# FullFuseSchem.net
KiCad netlist of a schematic drawn in Altium Designer
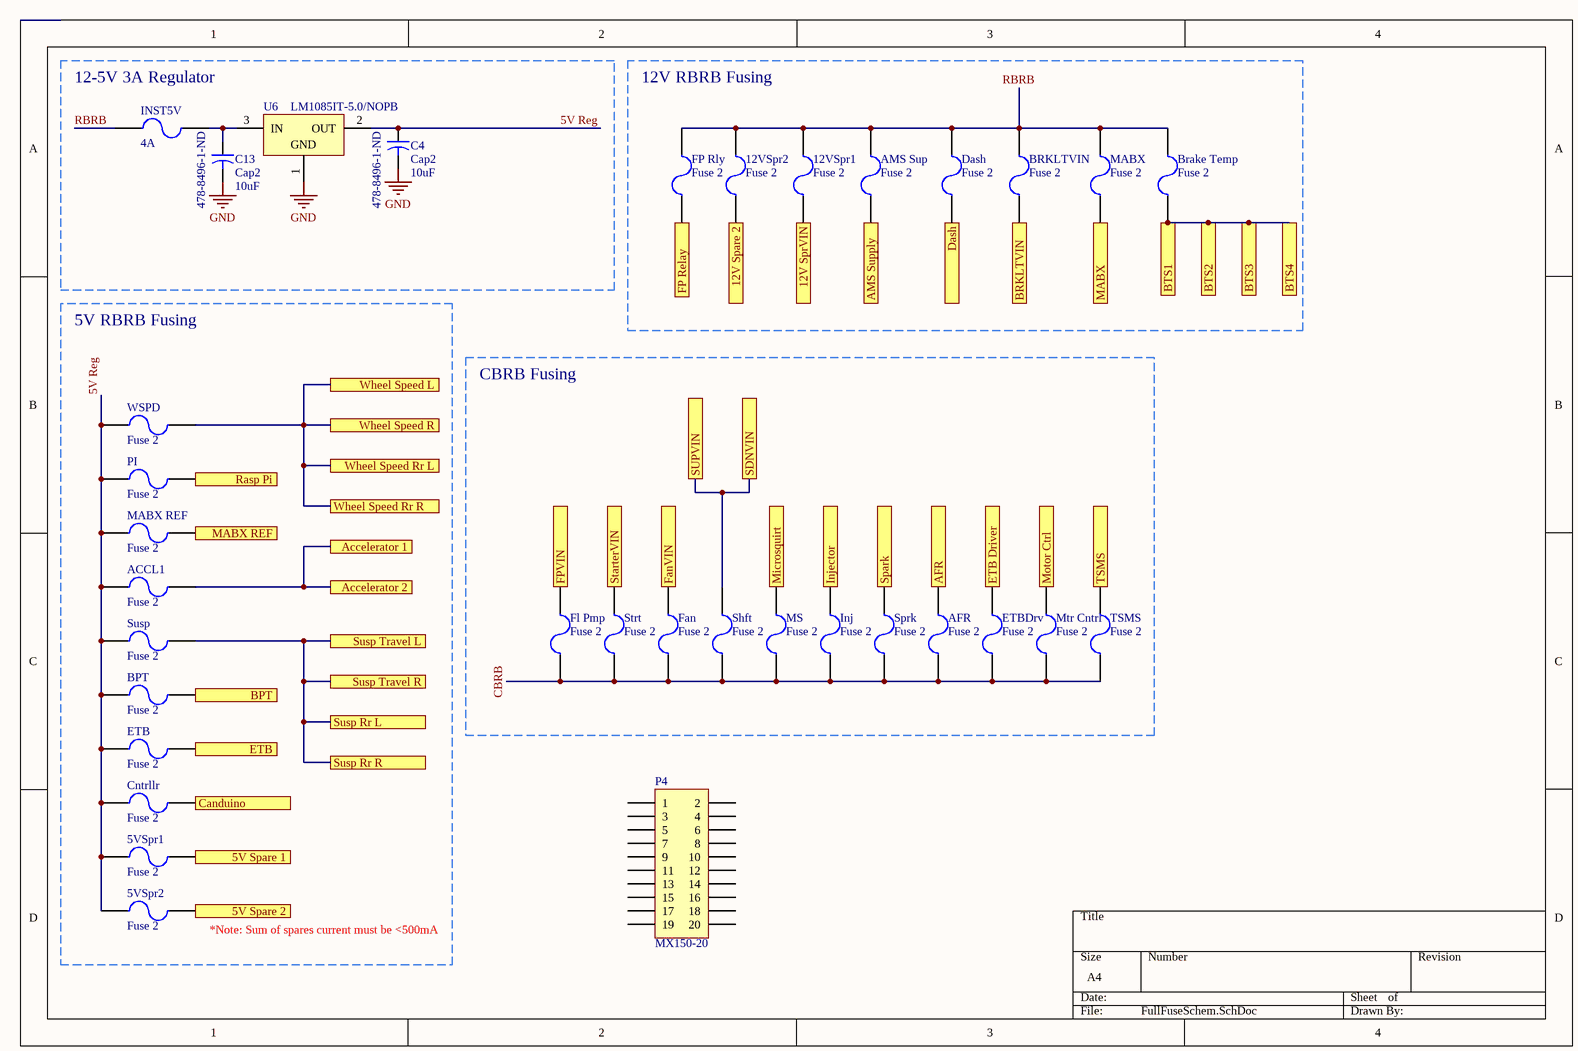
[diagram p0: FullFuseSchem.SchDoc]

(export (version "E")
  (design (tool "Eeschema 10.0.6"))
  (components
    (comp (ref "5VSpr1")
      (value "Fuse 2")
      (footprint "PIN-W2/E2.8")
      (description "Fuse")
      (fields (field (name "PUBLISHER") "Altium Limited"))
      (libsource (lib "Miscellaneous Devices") (part "Fuse 2"))
    )
    (comp (ref "5VSpr2")
      (value "Fuse 2")
      (footprint "PIN-W2/E2.8")
      (description "Fuse")
      (fields (field (name "PUBLISHER") "Altium Limited"))
      (libsource (lib "Miscellaneous Devices") (part "Fuse 2"))
    )
    (comp (ref "12VSpr1")
      (value "Fuse 2")
      (footprint "PIN-W2/E2.8")
      (description "Fuse")
      (fields (field (name "PUBLISHER") "Altium Limited"))
      (libsource (lib "Miscellaneous Devices") (part "Fuse 2"))
    )
    (comp (ref "12VSpr2")
      (value "Fuse 2")
      (footprint "PIN-W2/E2.8")
      (description "Fuse")
      (fields (field (name "PUBLISHER") "Altium Limited"))
      (libsource (lib "Miscellaneous Devices") (part "Fuse 2"))
    )
    (comp (ref "ACCL1")
      (value "Fuse 2")
      (footprint "FUSC4632X85N")
      (description "Fuse")
      (fields
        (field (name "PART NUMBER") "MF-MSMF050-2")
        (field (name "MANUFACTURER") "Bourns")
        (field (name "PUBLISHER") "Altium Limited")
      )
      (libsource (lib "PowerDistLib") (part "Fuse 2"))
    )
    (comp (ref "AFR")
      (value "Fuse 2")
      (footprint "FUSC4632X85N")
      (fields
        (field (name "PART NUMBER") "MF-MSMF050-2")
        (field (name "MANUFACTURER") "Bourns")
        (field (name "PUBLISHER") "Altium Limited")
      )
      (libsource (lib "PowerDistLib") (part "Fuse 2"))
    )
    (comp (ref "AMS Sup")
      (value "Fuse 2")
      (footprint "FUSC4632X85N")
      (description "Fuse")
      (fields
        (field (name "PART NUMBER") "MF-MSMF050-2")
        (field (name "MANUFACTURER") "Bourns")
        (field (name "PUBLISHER") "Altium Limited")
      )
      (libsource (lib "PowerDistLib") (part "Fuse 2"))
    )
    (comp (ref "BPT")
      (value "Fuse 2")
      (footprint "FUSC4632X85N")
      (description "Fuse")
      (fields
        (field (name "PART NUMBER") "MF-MSMF050-2")
        (field (name "MANUFACTURER") "Bourns")
        (field (name "PUBLISHER") "Altium Limited")
      )
      (libsource (lib "PowerDistLib") (part "Fuse 2"))
    )
    (comp (ref "Brake Temp")
      (value "Fuse 2")
      (footprint "FUSC4632X85N")
      (description "Fuse")
      (fields
        (field (name "PART NUMBER") "MF-MSMF050-2")
        (field (name "MANUFACTURER") "Bourns")
        (field (name "PUBLISHER") "Altium Limited")
      )
      (libsource (lib "PowerDistLib") (part "Fuse 2"))
    )
    (comp (ref "BRKLTVIN")
      (value "Fuse 2")
      (footprint "FUSC4632X85N")
      (description "Fuse")
      (fields
        (field (name "PART NUMBER") "MF-MSMF050-2")
        (field (name "MANUFACTURER") "Bourns")
        (field (name "PUBLISHER") "Altium Limited")
      )
      (libsource (lib "PowerDistLib") (part "Fuse 2"))
    )
    (comp (ref "C4")
      (value "Cap2")
      (footprint "C1206")
      (description "Capacitor. Ceramic 10uF 50V rating recommended, place close to pin")
      (fields
        (field (name "ALTIUM_VALUE") "10uF")
        (field (name "SUPPLIER PART NUMBER 1") "478-8496-1-ND")
        (field (name "PUBLISHER") "Altium Limited")
      )
      (libsource (lib "PowerDistLib") (part "Cap2"))
    )
    (comp (ref "C13")
      (value "Cap2")
      (footprint "C1206")
      (description "Capacitor. Ceramic 10uF 50V rating recommended, place close to pin")
      (fields
        (field (name "ALTIUM_VALUE") "10uF")
        (field (name "SUPPLIER PART NUMBER 1") "478-8496-1-ND")
        (field (name "PUBLISHER") "Altium Limited")
      )
      (libsource (lib "PowerDistLib") (part "Cap2"))
    )
    (comp (ref "Cntrllr")
      (value "Fuse 2")
      (footprint "PIN-W2/E2.8")
      (description "Fuse")
      (fields (field (name "PUBLISHER") "Altium Limited"))
      (libsource (lib "Miscellaneous Devices") (part "Fuse 2"))
    )
    (comp (ref "Dash")
      (value "Fuse 2")
      (footprint "FUSC4632X85N")
      (description "Fuse")
      (fields
        (field (name "PART NUMBER") "MF-MSMF050-2")
        (field (name "MANUFACTURER") "Bourns")
        (field (name "PUBLISHER") "Altium Limited")
      )
      (libsource (lib "PowerDistLib") (part "Fuse 2"))
    )
    (comp (ref "ETB")
      (value "Fuse 2")
      (footprint "FUSC4632X85N")
      (description "Fuse")
      (fields
        (field (name "PART NUMBER") "MF-MSMF050-2")
        (field (name "MANUFACTURER") "Bourns")
        (field (name "PUBLISHER") "Altium Limited")
      )
      (libsource (lib "PowerDistLib") (part "Fuse 2"))
    )
    (comp (ref "ETBDrv")
      (value "Fuse 2")
      (footprint "FUSC4632X85N")
      (description "Fuse")
      (fields
        (field (name "PART NUMBER") "MF-MSMF050-2")
        (field (name "MANUFACTURER") "Bourns")
        (field (name "PUBLISHER") "Altium Limited")
      )
      (libsource (lib "PowerDistLib") (part "Fuse 2"))
    )
    (comp (ref "Fan")
      (value "Fuse 2")
      (footprint "FUSC4632X85N")
      (description "Fuse")
      (fields
        (field (name "PART NUMBER") "MF-MSMF050-2")
        (field (name "MANUFACTURER") "Bourns")
        (field (name "PUBLISHER") "Altium Limited")
      )
      (libsource (lib "PowerDistLib") (part "Fuse 2"))
    )
    (comp (ref "Fl Pmp")
      (value "Fuse 2")
      (footprint "FUSC4632X85N")
      (description "Fuse")
      (fields
        (field (name "PART NUMBER") "MF-MSMF050-2")
        (field (name "MANUFACTURER") "Bourns")
        (field (name "PUBLISHER") "Altium Limited")
      )
      (libsource (lib "PowerDistLib") (part "Fuse 2"))
    )
    (comp (ref "FP Rly")
      (value "Fuse 2")
      (footprint "FUSC4632X85N")
      (description "Fuse")
      (fields
        (field (name "PART NUMBER") "MF-MSMF050-2")
        (field (name "MANUFACTURER") "Bourns")
        (field (name "PUBLISHER") "Altium Limited")
      )
      (libsource (lib "PowerDistLib") (part "Fuse 2"))
    )
    (comp (ref "Inj")
      (value "Fuse 2")
      (footprint "FUSC4632X85N")
      (description "Fuse")
      (fields
        (field (name "PART NUMBER") "MF-MSMF050-2")
        (field (name "MANUFACTURER") "Bourns")
        (field (name "PUBLISHER") "Altium Limited")
      )
      (libsource (lib "PowerDistLib") (part "Fuse 2"))
    )
    (comp (ref "INST5V")
      (value "4A")
      (footprint "FUSC4632X85N")
      (description "Fuse")
      (fields
        (field (name "PART NUMBER") "MF-MSMF050-2")
        (field (name "MANUFACTURER") "Bourns")
        (field (name "PUBLISHER") "Altium Limited")
      )
      (libsource (lib "PowerDistLib") (part "Fuse 2"))
    )
    (comp (ref "MABX")
      (value "Fuse 2")
      (footprint "FUSC4632X85N")
      (description "Fuse")
      (fields
        (field (name "PART NUMBER") "MF-MSMF050-2")
        (field (name "MANUFACTURER") "Bourns")
        (field (name "PUBLISHER") "Altium Limited")
      )
      (libsource (lib "PowerDistLib") (part "Fuse 2"))
    )
    (comp (ref "MABX REF")
      (value "Fuse 2")
      (footprint "FUSC4632X85N")
      (description "Fuse")
      (fields
        (field (name "PART NUMBER") "MF-MSMF050-2")
        (field (name "MANUFACTURER") "Bourns")
        (field (name "PUBLISHER") "Altium Limited")
      )
      (libsource (lib "PowerDistLib") (part "Fuse 2"))
    )
    (comp (ref "MS")
      (value "Fuse 2")
      (footprint "FUSC4632X85N")
      (description "Fuse")
      (fields
        (field (name "PART NUMBER") "MF-MSMF050-2")
        (field (name "MANUFACTURER") "Bourns")
        (field (name "PUBLISHER") "Altium Limited")
      )
      (libsource (lib "PowerDistLib") (part "Fuse 2"))
    )
    (comp (ref "Mtr Cntrl")
      (value "Fuse 2")
      (footprint "FUSC4632X85N")
      (description "Fuse")
      (fields
        (field (name "PART NUMBER") "MF-MSMF050-2")
        (field (name "MANUFACTURER") "Bourns")
        (field (name "PUBLISHER") "Altium Limited")
      )
      (libsource (lib "PowerDistLib") (part "Fuse 2"))
    )
    (comp (ref "P4")
      (value "MX150-20")
      (footprint "HDR2X10")
      (description "Header, 10-Pin, Dual row")
      (fields (field (name "PUBLISHER") "Altium Limited"))
      (libsource (lib "PowerDistLib") (part "Header 10X2"))
    )
    (comp (ref "PI")
      (value "Fuse 2")
      (footprint "FUSC4632X85N")
      (description "Fuse")
      (fields
        (field (name "PART NUMBER") "MF-MSMF050-2")
        (field (name "MANUFACTURER") "Bourns")
        (field (name "PUBLISHER") "Altium Limited")
      )
      (libsource (lib "PowerDistLib") (part "Fuse 2"))
    )
    (comp (ref "Shft")
      (value "Fuse 2")
      (footprint "FUSC4632X85N")
      (description "Fuse")
      (fields
        (field (name "PART NUMBER") "MF-MSMF050-2")
        (field (name "MANUFACTURER") "Bourns")
        (field (name "PUBLISHER") "Altium Limited")
      )
      (libsource (lib "PowerDistLib") (part "Fuse 2"))
    )
    (comp (ref "Sprk")
      (value "Fuse 2")
      (footprint "FUSC4632X85N")
      (description "Fuse")
      (fields
        (field (name "PART NUMBER") "MF-MSMF050-2")
        (field (name "MANUFACTURER") "Bourns")
        (field (name "PUBLISHER") "Altium Limited")
      )
      (libsource (lib "PowerDistLib") (part "Fuse 2"))
    )
    (comp (ref "Strt")
      (value "Fuse 2")
      (footprint "FUSC4632X85N")
      (description "Fuse")
      (fields
        (field (name "PART NUMBER") "MF-MSMF050-2")
        (field (name "MANUFACTURER") "Bourns")
        (field (name "PUBLISHER") "Altium Limited")
      )
      (libsource (lib "PowerDistLib") (part "Fuse 2"))
    )
    (comp (ref "Susp")
      (value "Fuse 2")
      (footprint "FUSC4632X85N")
      (description "Fuse")
      (fields
        (field (name "PART NUMBER") "MF-MSMF050-2")
        (field (name "MANUFACTURER") "Bourns")
        (field (name "PUBLISHER") "Altium Limited")
      )
      (libsource (lib "PowerDistLib") (part "Fuse 2"))
    )
    (comp (ref "TSMS")
      (value "Fuse 2")
      (footprint "FUSC4632X85N")
      (description "Fuse")
      (fields
        (field (name "PART NUMBER") "MF-MSMF050-2")
        (field (name "MANUFACTURER") "Bourns")
        (field (name "PUBLISHER") "Altium Limited")
      )
      (libsource (lib "PowerDistLib") (part "Fuse 2"))
    )
    (comp (ref "U6")
      (value "LM1085IT-5.0/NOPB")
      (footprint "T03B")
      (description "3A Low Dropout Positive Regulators, 3-pin TO-220, Pb-Free")
      (fields (field (name "MANUFACTURER") "National Semiconductor"))
      (libsource (lib "PowerDistLib") (part "LM1085IT-5.0/NOPB"))
    )
    (comp (ref "WSPD")
      (value "Fuse 2")
      (footprint "FUSC4632X85N")
      (description "Fuse")
      (fields
        (field (name "PART NUMBER") "MF-MSMF050-2")
        (field (name "MANUFACTURER") "Bourns")
        (field (name "PUBLISHER") "Altium Limited")
      )
      (libsource (lib "PowerDistLib") (part "Fuse 2"))
    )
  )
  (nets
    (net (code "1") (name "/5V Reg") (class "Default")
      (node (ref "5VSpr1") (pin "1") (pinfunction "1_1") (pintype "passive"))
      (node (ref "5VSpr2") (pin "1") (pinfunction "1_1") (pintype "passive"))
      (node (ref "ACCL1") (pin "1") (pinfunction "1_1") (pintype "passive"))
      (node (ref "BPT") (pin "1") (pinfunction "1_1") (pintype "passive"))
      (node (ref "C4") (pin "1") (pinfunction "1_1") (pintype "passive"))
      (node (ref "Cntrllr") (pin "1") (pinfunction "1_1") (pintype "passive"))
      (node (ref "ETB") (pin "1") (pinfunction "1_1") (pintype "passive"))
      (node (ref "MABX REF") (pin "1") (pinfunction "1_1") (pintype "passive"))
      (node (ref "PI") (pin "1") (pinfunction "1_1") (pintype "passive"))
      (node (ref "Susp") (pin "1") (pinfunction "1_1") (pintype "passive"))
      (node (ref "U6") (pin "2") (pinfunction "OUT_2") (pintype "power_in"))
      (node (ref "WSPD") (pin "1") (pinfunction "1_1") (pintype "passive"))
    )
    (net (code "2") (name "/5V Spare 1") (class "Default")
      (node (ref "5VSpr1") (pin "2") (pinfunction "2_2") (pintype "passive"))
    )
    (net (code "3") (name "/5V Spare 2") (class "Default")
      (node (ref "5VSpr2") (pin "2") (pinfunction "2_2") (pintype "passive"))
    )
    (net (code "4") (name "/12V Spare 2") (class "Default")
      (node (ref "12VSpr2") (pin "1") (pinfunction "1_1") (pintype "passive"))
    )
    (net (code "5") (name "/12V SprVIN") (class "Default")
      (node (ref "12VSpr1") (pin "1") (pinfunction "1_1") (pintype "passive"))
    )
    (net (code "6") (name "/AFR") (class "Default")
      (node (ref "AFR") (pin "2") (pinfunction "2_2") (pintype "passive"))
    )
    (net (code "7") (name "/AMS Supply") (class "Default")
      (node (ref "AMS Sup") (pin "1") (pinfunction "1_1") (pintype "passive"))
    )
    (net (code "8") (name "/Accelerator 1") (class "Default")
      (node (ref "ACCL1") (pin "2") (pinfunction "2_2") (pintype "passive"))
    )
    (net (code "9") (name "/BPT") (class "Default")
      (node (ref "BPT") (pin "2") (pinfunction "2_2") (pintype "passive"))
    )
    (net (code "10") (name "/BRKLTVIN") (class "Default")
      (node (ref "BRKLTVIN") (pin "1") (pinfunction "1_1") (pintype "passive"))
    )
    (net (code "11") (name "/BTS1") (class "Default")
      (node (ref "Brake Temp") (pin "1") (pinfunction "1_1") (pintype "passive"))
    )
    (net (code "12") (name "/CBRB") (class "Default")
      (node (ref "AFR") (pin "1") (pinfunction "1_1") (pintype "passive"))
      (node (ref "ETBDrv") (pin "1") (pinfunction "1_1") (pintype "passive"))
      (node (ref "Fan") (pin "1") (pinfunction "1_1") (pintype "passive"))
      (node (ref "Fl Pmp") (pin "1") (pinfunction "1_1") (pintype "passive"))
      (node (ref "Inj") (pin "1") (pinfunction "1_1") (pintype "passive"))
      (node (ref "MS") (pin "1") (pinfunction "1_1") (pintype "passive"))
      (node (ref "Mtr Cntrl") (pin "1") (pinfunction "1_1") (pintype "passive"))
      (node (ref "Shft") (pin "1") (pinfunction "1_1") (pintype "passive"))
      (node (ref "Sprk") (pin "1") (pinfunction "1_1") (pintype "passive"))
      (node (ref "Strt") (pin "1") (pinfunction "1_1") (pintype "passive"))
      (node (ref "TSMS") (pin "1") (pinfunction "1_1") (pintype "passive"))
    )
    (net (code "13") (name "/Canduino") (class "Default")
      (node (ref "Cntrllr") (pin "2") (pinfunction "2_2") (pintype "passive"))
    )
    (net (code "14") (name "/Dash") (class "Default")
      (node (ref "Dash") (pin "1") (pinfunction "1_1") (pintype "passive"))
    )
    (net (code "15") (name "/ETB") (class "Default")
      (node (ref "ETB") (pin "2") (pinfunction "2_2") (pintype "passive"))
    )
    (net (code "16") (name "/ETB Driver") (class "Default")
      (node (ref "ETBDrv") (pin "2") (pinfunction "2_2") (pintype "passive"))
    )
    (net (code "17") (name "/FP Relay") (class "Default")
      (node (ref "FP Rly") (pin "1") (pinfunction "1_1") (pintype "passive"))
    )
    (net (code "18") (name "/FPVIN") (class "Default")
      (node (ref "Fl Pmp") (pin "2") (pinfunction "2_2") (pintype "passive"))
    )
    (net (code "19") (name "/FanVIN") (class "Default")
      (node (ref "Fan") (pin "2") (pinfunction "2_2") (pintype "passive"))
    )
    (net (code "20") (name "/Injector") (class "Default")
      (node (ref "Inj") (pin "2") (pinfunction "2_2") (pintype "passive"))
    )
    (net (code "21") (name "/MABX") (class "Default")
      (node (ref "MABX") (pin "1") (pinfunction "1_1") (pintype "passive"))
    )
    (net (code "22") (name "/MABX REF") (class "Default")
      (node (ref "MABX REF") (pin "2") (pinfunction "2_2") (pintype "passive"))
    )
    (net (code "23") (name "/Microsquirt") (class "Default")
      (node (ref "MS") (pin "2") (pinfunction "2_2") (pintype "passive"))
    )
    (net (code "24") (name "/Motor Ctrl") (class "Default")
      (node (ref "Mtr Cntrl") (pin "2") (pinfunction "2_2") (pintype "passive"))
    )
    (net (code "25") (name "/RBRB") (class "Default")
      (node (ref "12VSpr1") (pin "2") (pinfunction "2_2") (pintype "passive"))
      (node (ref "12VSpr2") (pin "2") (pinfunction "2_2") (pintype "passive"))
      (node (ref "AMS Sup") (pin "2") (pinfunction "2_2") (pintype "passive"))
      (node (ref "BRKLTVIN") (pin "2") (pinfunction "2_2") (pintype "passive"))
      (node (ref "Brake Temp") (pin "2") (pinfunction "2_2") (pintype "passive"))
      (node (ref "Dash") (pin "2") (pinfunction "2_2") (pintype "passive"))
      (node (ref "FP Rly") (pin "2") (pinfunction "2_2") (pintype "passive"))
      (node (ref "INST5V") (pin "2") (pinfunction "2_2") (pintype "passive"))
      (node (ref "MABX") (pin "2") (pinfunction "2_2") (pintype "passive"))
    )
    (net (code "26") (name "/Rasp Pi") (class "Default")
      (node (ref "PI") (pin "2") (pinfunction "2_2") (pintype "passive"))
    )
    (net (code "27") (name "/SDNVIN") (class "Default")
      (node (ref "Shft") (pin "2") (pinfunction "2_2") (pintype "passive"))
    )
    (net (code "28") (name "/Spark") (class "Default")
      (node (ref "Sprk") (pin "2") (pinfunction "2_2") (pintype "passive"))
    )
    (net (code "29") (name "/StarterVIN") (class "Default")
      (node (ref "Strt") (pin "2") (pinfunction "2_2") (pintype "passive"))
    )
    (net (code "30") (name "/Susp Rr L") (class "Default")
      (node (ref "Susp") (pin "2") (pinfunction "2_2") (pintype "passive"))
    )
    (net (code "31") (name "/TSMS") (class "Default")
      (node (ref "TSMS") (pin "2") (pinfunction "2_2") (pintype "passive"))
    )
    (net (code "32") (name "/Wheel Speed L") (class "Default")
      (node (ref "WSPD") (pin "2") (pinfunction "2_2") (pintype "passive"))
    )
    (net (code "33") (name "GND") (class "Default")
      (node (ref "C13") (pin "2") (pinfunction "2_2") (pintype "passive"))
      (node (ref "C4") (pin "2") (pinfunction "2_2") (pintype "passive"))
      (node (ref "U6") (pin "1") (pinfunction "GND_1") (pintype "power_in"))
    )
    (net (code "34") (name "Net-(U6-IN)") (class "Default")
      (node (ref "C13") (pin "1") (pinfunction "1_1") (pintype "passive"))
      (node (ref "INST5V") (pin "1") (pinfunction "1_1") (pintype "passive"))
      (node (ref "U6") (pin "3") (pinfunction "IN_3") (pintype "power_in"))
    )
    (net (code "35") (name "unconnected-(P4-Pad1)") (class "Default")
      (node (ref "P4") (pin "1") (pinfunction "1_1") (pintype "passive"))
    )
    (net (code "36") (name "unconnected-(P4-Pad2)") (class "Default")
      (node (ref "P4") (pin "2") (pinfunction "2_2") (pintype "passive"))
    )
    (net (code "37") (name "unconnected-(P4-Pad3)") (class "Default")
      (node (ref "P4") (pin "3") (pinfunction "3_3") (pintype "passive"))
    )
    (net (code "38") (name "unconnected-(P4-Pad4)") (class "Default")
      (node (ref "P4") (pin "4") (pinfunction "4_4") (pintype "passive"))
    )
    (net (code "39") (name "unconnected-(P4-Pad5)") (class "Default")
      (node (ref "P4") (pin "5") (pinfunction "5_5") (pintype "passive"))
    )
    (net (code "40") (name "unconnected-(P4-Pad6)") (class "Default")
      (node (ref "P4") (pin "6") (pinfunction "6_6") (pintype "passive"))
    )
    (net (code "41") (name "unconnected-(P4-Pad7)") (class "Default")
      (node (ref "P4") (pin "7") (pinfunction "7_7") (pintype "passive"))
    )
    (net (code "42") (name "unconnected-(P4-Pad8)") (class "Default")
      (node (ref "P4") (pin "8") (pinfunction "8_8") (pintype "passive"))
    )
    (net (code "43") (name "unconnected-(P4-Pad9)") (class "Default")
      (node (ref "P4") (pin "9") (pinfunction "9_9") (pintype "passive"))
    )
    (net (code "44") (name "unconnected-(P4-Pad10)") (class "Default")
      (node (ref "P4") (pin "10") (pinfunction "10_10") (pintype "passive"))
    )
    (net (code "45") (name "unconnected-(P4-Pad11)") (class "Default")
      (node (ref "P4") (pin "11") (pinfunction "11_11") (pintype "passive"))
    )
    (net (code "46") (name "unconnected-(P4-Pad12)") (class "Default")
      (node (ref "P4") (pin "12") (pinfunction "12_12") (pintype "passive"))
    )
    (net (code "47") (name "unconnected-(P4-Pad13)") (class "Default")
      (node (ref "P4") (pin "13") (pinfunction "13_13") (pintype "passive"))
    )
    (net (code "48") (name "unconnected-(P4-Pad14)") (class "Default")
      (node (ref "P4") (pin "14") (pinfunction "14_14") (pintype "passive"))
    )
    (net (code "49") (name "unconnected-(P4-Pad15)") (class "Default")
      (node (ref "P4") (pin "15") (pinfunction "15_15") (pintype "passive"))
    )
    (net (code "50") (name "unconnected-(P4-Pad16)") (class "Default")
      (node (ref "P4") (pin "16") (pinfunction "16_16") (pintype "passive"))
    )
    (net (code "51") (name "unconnected-(P4-Pad17)") (class "Default")
      (node (ref "P4") (pin "17") (pinfunction "17_17") (pintype "passive"))
    )
    (net (code "52") (name "unconnected-(P4-Pad18)") (class "Default")
      (node (ref "P4") (pin "18") (pinfunction "18_18") (pintype "passive"))
    )
    (net (code "53") (name "unconnected-(P4-Pad19)") (class "Default")
      (node (ref "P4") (pin "19") (pinfunction "19_19") (pintype "passive"))
    )
    (net (code "54") (name "unconnected-(P4-Pad20)") (class "Default")
      (node (ref "P4") (pin "20") (pinfunction "20_20") (pintype "passive"))
    )
  )
)
